# Ocreeb_MK_2__faders_half__schematic.net
KiCad netlist of a schematic drawn in EAGLE
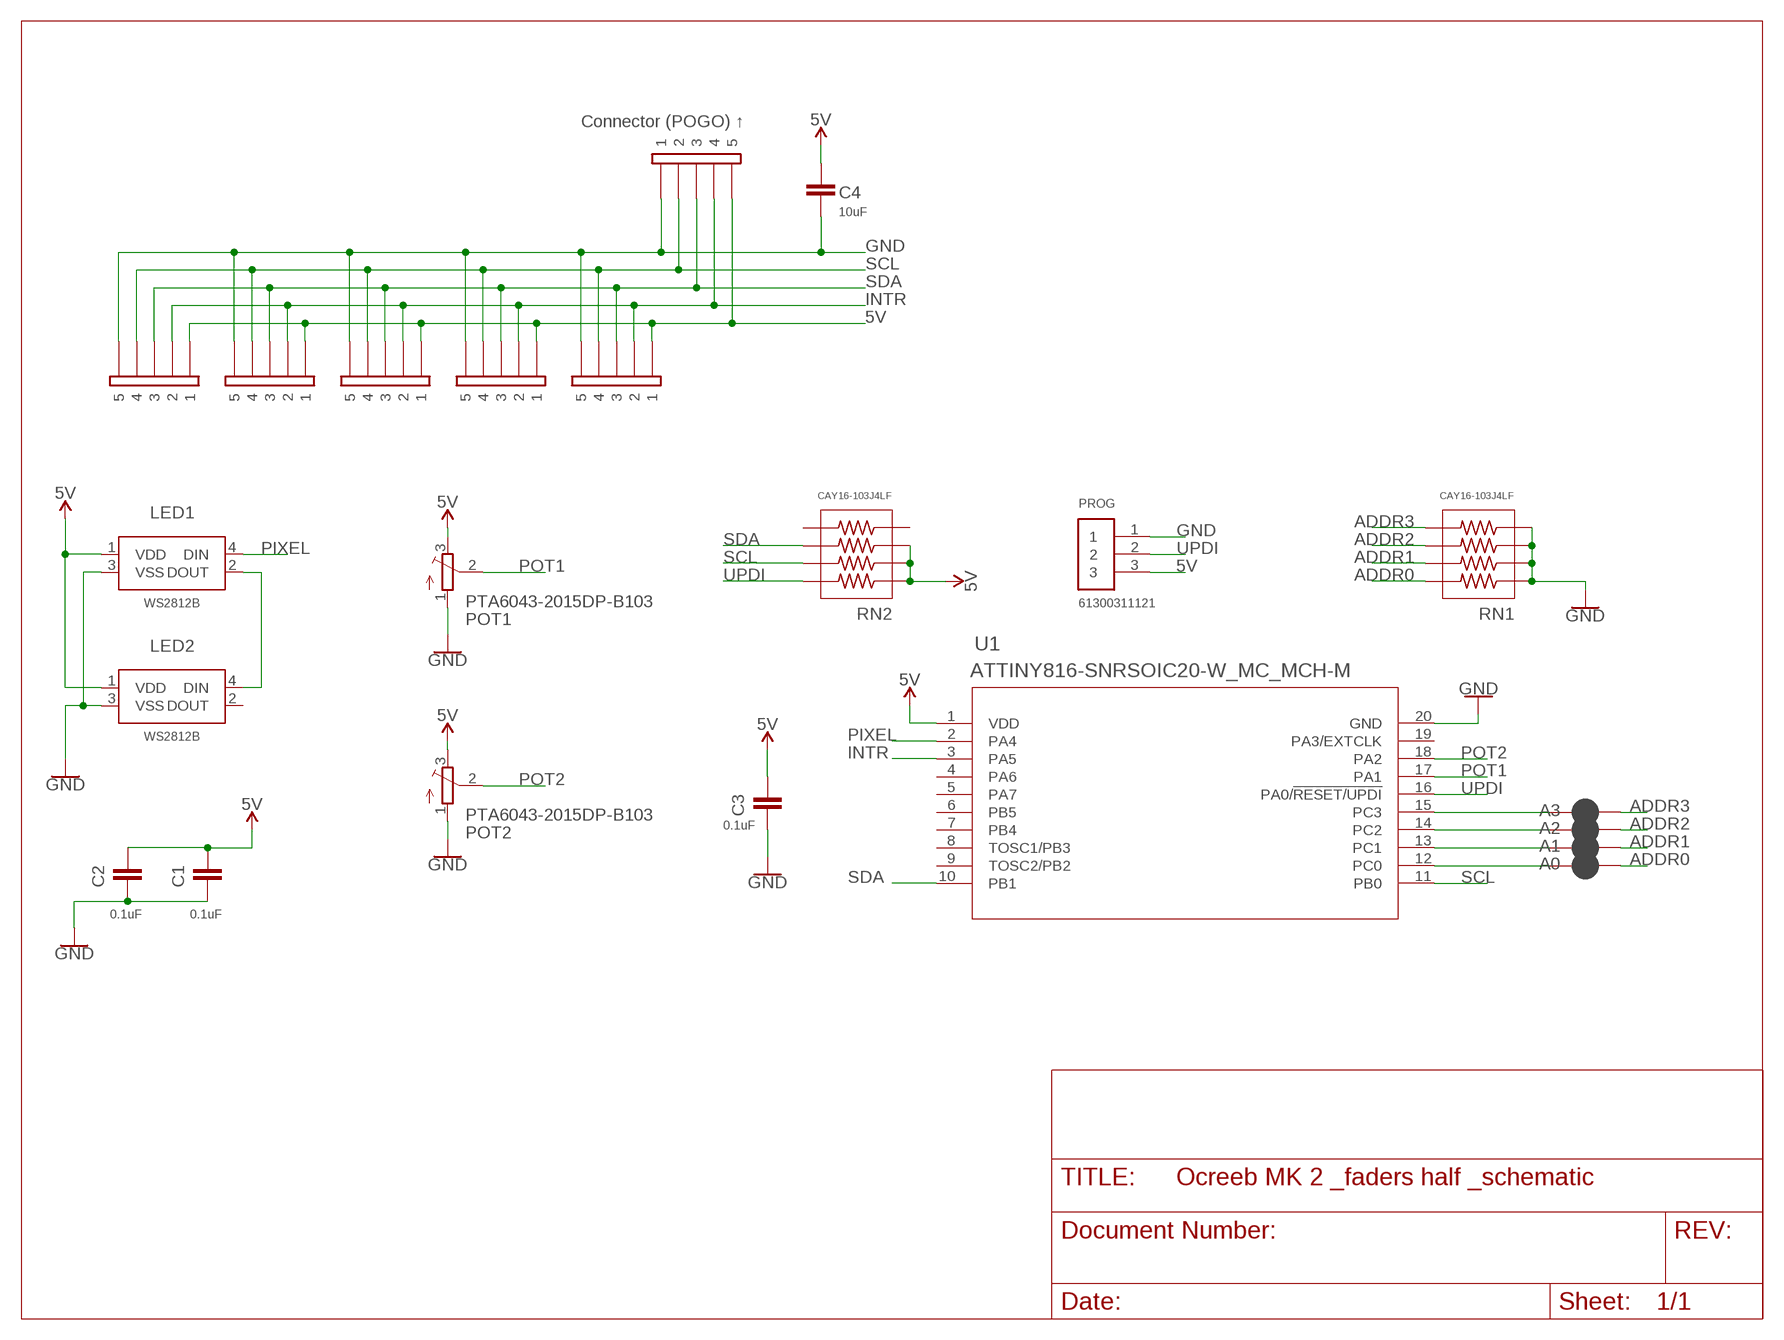
[diagram p0: schematic, sheet 1]

(export (version "E")
  (design (tool "Eeschema 10.0.6"))
  (components
    (comp (ref "A0")
      (value "JUMPER-SMT_2_NC_PASTE_SILK")
      (footprint "eagle-import:SMT-JUMPER_2_NC_PASTE_SILK")
      (libsource (lib "eagle-import") (part "JUMPER-SMT_2_NC_PASTE_SILK"))
    )
    (comp (ref "A1")
      (value "JUMPER-SMT_2_NC_PASTE_SILK")
      (footprint "eagle-import:SMT-JUMPER_2_NC_PASTE_SILK")
      (libsource (lib "eagle-import") (part "JUMPER-SMT_2_NC_PASTE_SILK"))
    )
    (comp (ref "A2")
      (value "JUMPER-SMT_2_NC_PASTE_SILK")
      (footprint "eagle-import:SMT-JUMPER_2_NC_PASTE_SILK")
      (libsource (lib "eagle-import") (part "JUMPER-SMT_2_NC_PASTE_SILK"))
    )
    (comp (ref "A3")
      (value "JUMPER-SMT_2_NC_PASTE_SILK")
      (footprint "eagle-import:SMT-JUMPER_2_NC_PASTE_SILK")
      (libsource (lib "eagle-import") (part "JUMPER-SMT_2_NC_PASTE_SILK"))
    )
    (comp (ref "C1")
      (value "0.1uF")
      (footprint "eagle-import:CAPC1608X85")
      (libsource (lib "eagle-import") (part "CCHIP-0603(1608-METRIC)_"))
    )
    (comp (ref "C2")
      (value "0.1uF")
      (footprint "eagle-import:CAPC1608X85")
      (libsource (lib "eagle-import") (part "CCHIP-0603(1608-METRIC)_"))
    )
    (comp (ref "C3")
      (value "0.1uF")
      (footprint "eagle-import:CAPC1608X85")
      (libsource (lib "eagle-import") (part "CCHIP-0603(1608-METRIC)_"))
    )
    (comp (ref "C4")
      (value "10uF")
      (footprint "eagle-import:CAPC2012X110")
      (libsource (lib "eagle-import") (part "CCHIP-0805(2012-METRIC)_"))
    )
    (comp (ref "LED1")
      (value "WS2812B")
      (footprint "eagle-import:WS2812B")
      (fields (field (name "MANUFACTURER") "Worldsemi"))
      (libsource (lib "eagle-import") (part "WS2812B"))
    )
    (comp (ref "LED2")
      (value "WS2812B")
      (footprint "eagle-import:WS2812B")
      (fields (field (name "MANUFACTURER") "Worldsemi"))
      (libsource (lib "eagle-import") (part "WS2812B"))
    )
    (comp (ref "POT1")
      (value "PTA6043-2015DP-B103")
      (footprint "eagle-import:PTA6043-2015DP-B103")
      (fields (field (name "MF") "Bourns") (field (name "MP") "PTA6043-2015DPB103"))
      (libsource (lib "eagle-import") (part "PTA6043-2015DP-B103"))
    )
    (comp (ref "POT2")
      (value "PTA6043-2015DP-B103")
      (footprint "eagle-import:PTA6043-2015DP-B103")
      (fields (field (name "MF") "Bourns") (field (name "MP") "PTA6043-2015DPB103"))
      (libsource (lib "eagle-import") (part "PTA6043-2015DP-B103"))
    )
    (comp (ref "PROG")
      (value "61300311121")
      (footprint "eagle-import:61300311121")
      (fields
        (field (name "DIGI_KEY_PART_NUMBER") "732-5316-ND")
        (field (name "MANUFACTURER") "Wurth Electronics Inc.")
        (field (name "CREATED_BY") "PCBLayout.com")
      )
      (libsource (lib "eagle-import") (part "61300311121"))
    )
    (comp (ref "RN1")
      (value "CAY16-103J4LF")
      (footprint "eagle-import:RESCAF80P320X160X60-8N")
      (fields (field (name "DIGIKEY_PART_NUMBER") "CAY16-103J4LFTR-ND") (field (name "MF") "Bourns"))
      (libsource (lib "eagle-import") (part "CAY16-103J4LF"))
    )
    (comp (ref "RN2")
      (value "CAY16-103J4LF")
      (footprint "eagle-import:RESCAF80P320X160X60-8N")
      (fields (field (name "DIGIKEY_PART_NUMBER") "CAY16-103J4LFTR-ND") (field (name "MF") "Bourns"))
      (libsource (lib "eagle-import") (part "CAY16-103J4LF"))
    )
    (comp (ref "U$1")
      (value "5PIN_EDGE5_POGO_EDGE_OUT_")
      (footprint "eagle-import:5_POGO_EDGE")
      (libsource (lib "eagle-import") (part "5PIN_EDGE5_POGO_EDGE_OUT_"))
    )
    (comp (ref "U$2")
      (value "5PIN_EDGE")
      (footprint "eagle-import:5_POGO_EDGE")
      (libsource (lib "eagle-import") (part "5PIN_EDGE"))
    )
    (comp (ref "U$3")
      (value "5PIN_EDGE")
      (footprint "eagle-import:5_POGO_EDGE")
      (libsource (lib "eagle-import") (part "5PIN_EDGE"))
    )
    (comp (ref "U$4")
      (value "5PIN_EDGE")
      (footprint "eagle-import:5_POGO_EDGE")
      (libsource (lib "eagle-import") (part "5PIN_EDGE"))
    )
    (comp (ref "U$5")
      (value "5PIN_EDGE")
      (footprint "eagle-import:5_POGO_EDGE")
      (libsource (lib "eagle-import") (part "5PIN_EDGE"))
    )
    (comp (ref "U$6")
      (value "5PIN_EDGE")
      (footprint "eagle-import:5_POGO_EDGE")
      (libsource (lib "eagle-import") (part "5PIN_EDGE"))
    )
    (comp (ref "U1")
      (value "ATTINY816-SNRSOIC20-W_MC_MCH-M")
      (footprint "eagle-import:SOIC20-W_MC_MCH-M")
      (fields
        (field (name "MANUFACTURER_PART_NUMBER") "ATTINY816-SNR")
        (field (name "COPYRIGHT") "Copyright (C) 2023 Ultra Librarian. All rights reserved.")
      )
      (libsource (lib "eagle-import") (part "ATTINY816-SNRSOIC20-W_MC_MCH-M"))
    )
  )
  (nets
    (net (code "1") (name "/ADDR0") (class "Default")
      (node (ref "A0") (pin "1") (pinfunction "1_1") (pintype "passive"))
      (node (ref "RN1") (pin "8") (pinfunction "8_8") (pintype "passive"))
    )
    (net (code "2") (name "/ADDR1") (class "Default")
      (node (ref "A1") (pin "1") (pinfunction "1_1") (pintype "passive"))
      (node (ref "RN1") (pin "7") (pinfunction "7_7") (pintype "passive"))
    )
    (net (code "3") (name "/ADDR2") (class "Default")
      (node (ref "A2") (pin "1") (pinfunction "1_1") (pintype "passive"))
      (node (ref "RN1") (pin "6") (pinfunction "6_6") (pintype "passive"))
    )
    (net (code "4") (name "/ADDR3") (class "Default")
      (node (ref "A3") (pin "1") (pinfunction "1_1") (pintype "passive"))
      (node (ref "RN1") (pin "5") (pinfunction "5_5") (pintype "passive"))
    )
    (net (code "5") (name "/INTR") (class "Default")
      (node (ref "U$1") (pin "4") (pinfunction "4_4") (pintype "bidirectional"))
      (node (ref "U$2") (pin "2") (pinfunction "2_2") (pintype "bidirectional"))
      (node (ref "U$3") (pin "2") (pinfunction "2_2") (pintype "bidirectional"))
      (node (ref "U$4") (pin "2") (pinfunction "2_2") (pintype "bidirectional"))
      (node (ref "U$5") (pin "2") (pinfunction "2_2") (pintype "bidirectional"))
      (node (ref "U$6") (pin "2") (pinfunction "2_2") (pintype "bidirectional"))
      (node (ref "U1") (pin "3") (pinfunction "PA5_3") (pintype "bidirectional"))
    )
    (net (code "6") (name "/PIXEL") (class "Default")
      (node (ref "LED1") (pin "4") (pinfunction "DIN_4") (pintype "input"))
      (node (ref "U1") (pin "2") (pinfunction "PA4_2") (pintype "bidirectional"))
    )
    (net (code "7") (name "/POT1") (class "Default")
      (node (ref "POT1") (pin "2") (pinfunction "2_2") (pintype "passive"))
      (node (ref "U1") (pin "17") (pinfunction "PA1_17") (pintype "bidirectional"))
    )
    (net (code "8") (name "/POT2") (class "Default")
      (node (ref "POT2") (pin "2") (pinfunction "2_2") (pintype "passive"))
      (node (ref "U1") (pin "18") (pinfunction "PA2_18") (pintype "bidirectional"))
    )
    (net (code "9") (name "/SCL") (class "Default")
      (node (ref "RN2") (pin "7") (pinfunction "7_7") (pintype "passive"))
      (node (ref "U$1") (pin "2") (pinfunction "2_2") (pintype "bidirectional"))
      (node (ref "U$2") (pin "4") (pinfunction "4_4") (pintype "bidirectional"))
      (node (ref "U$3") (pin "4") (pinfunction "4_4") (pintype "bidirectional"))
      (node (ref "U$4") (pin "4") (pinfunction "4_4") (pintype "bidirectional"))
      (node (ref "U$5") (pin "4") (pinfunction "4_4") (pintype "bidirectional"))
      (node (ref "U$6") (pin "4") (pinfunction "4_4") (pintype "bidirectional"))
      (node (ref "U1") (pin "11") (pinfunction "PB0_11") (pintype "bidirectional"))
    )
    (net (code "10") (name "/SDA") (class "Default")
      (node (ref "RN2") (pin "6") (pinfunction "6_6") (pintype "passive"))
      (node (ref "U$1") (pin "3") (pinfunction "3_3") (pintype "bidirectional"))
      (node (ref "U$2") (pin "3") (pinfunction "3_3") (pintype "bidirectional"))
      (node (ref "U$3") (pin "3") (pinfunction "3_3") (pintype "bidirectional"))
      (node (ref "U$4") (pin "3") (pinfunction "3_3") (pintype "bidirectional"))
      (node (ref "U$5") (pin "3") (pinfunction "3_3") (pintype "bidirectional"))
      (node (ref "U$6") (pin "3") (pinfunction "3_3") (pintype "bidirectional"))
      (node (ref "U1") (pin "10") (pinfunction "PB1_10") (pintype "bidirectional"))
    )
    (net (code "11") (name "/UPDI") (class "Default")
      (node (ref "PROG") (pin "2") (pinfunction "2_2") (pintype "passive"))
      (node (ref "RN2") (pin "8") (pinfunction "8_8") (pintype "passive"))
      (node (ref "U1") (pin "16") (pinfunction "PA0/~{RESET/UPDI}_16") (pintype "bidirectional"))
    )
    (net (code "12") (name "5V") (class "Default")
      (node (ref "C1") (pin "2") (pinfunction "2_2") (pintype "passive"))
      (node (ref "C2") (pin "2") (pinfunction "2_2") (pintype "passive"))
      (node (ref "C3") (pin "2") (pinfunction "2_2") (pintype "passive"))
      (node (ref "C4") (pin "2") (pinfunction "2_2") (pintype "passive"))
      (node (ref "LED1") (pin "1") (pinfunction "VDD_1") (pintype "power_in"))
      (node (ref "LED2") (pin "1") (pinfunction "VDD_1") (pintype "power_in"))
      (node (ref "POT1") (pin "3") (pinfunction "3_3") (pintype "passive"))
      (node (ref "POT2") (pin "3") (pinfunction "3_3") (pintype "passive"))
      (node (ref "PROG") (pin "3") (pinfunction "3_3") (pintype "passive"))
      (node (ref "RN2") (pin "1") (pinfunction "1_1") (pintype "passive"))
      (node (ref "RN2") (pin "2") (pinfunction "2_2") (pintype "passive"))
      (node (ref "RN2") (pin "3") (pinfunction "3_3") (pintype "passive"))
      (node (ref "U$1") (pin "5") (pinfunction "5_5") (pintype "bidirectional"))
      (node (ref "U$2") (pin "1") (pinfunction "1_1") (pintype "bidirectional"))
      (node (ref "U$3") (pin "1") (pinfunction "1_1") (pintype "bidirectional"))
      (node (ref "U$4") (pin "1") (pinfunction "1_1") (pintype "bidirectional"))
      (node (ref "U$5") (pin "1") (pinfunction "1_1") (pintype "bidirectional"))
      (node (ref "U$6") (pin "1") (pinfunction "1_1") (pintype "bidirectional"))
      (node (ref "U1") (pin "1") (pinfunction "VDD_1") (pintype "power_in"))
    )
    (net (code "13") (name "GND") (class "Default")
      (node (ref "C1") (pin "1") (pinfunction "1_1") (pintype "passive"))
      (node (ref "C2") (pin "1") (pinfunction "1_1") (pintype "passive"))
      (node (ref "C3") (pin "1") (pinfunction "1_1") (pintype "passive"))
      (node (ref "C4") (pin "1") (pinfunction "1_1") (pintype "passive"))
      (node (ref "LED1") (pin "3") (pinfunction "VSS_3") (pintype "power_in"))
      (node (ref "LED2") (pin "3") (pinfunction "VSS_3") (pintype "power_in"))
      (node (ref "POT1") (pin "1") (pinfunction "1_1") (pintype "passive"))
      (node (ref "POT2") (pin "1") (pinfunction "1_1") (pintype "passive"))
      (node (ref "PROG") (pin "1") (pinfunction "1_1") (pintype "passive"))
      (node (ref "RN1") (pin "1") (pinfunction "1_1") (pintype "passive"))
      (node (ref "RN1") (pin "2") (pinfunction "2_2") (pintype "passive"))
      (node (ref "RN1") (pin "3") (pinfunction "3_3") (pintype "passive"))
      (node (ref "RN1") (pin "4") (pinfunction "4_4") (pintype "passive"))
      (node (ref "U$1") (pin "1") (pinfunction "1_1") (pintype "bidirectional"))
      (node (ref "U$2") (pin "5") (pinfunction "5_5") (pintype "bidirectional"))
      (node (ref "U$3") (pin "5") (pinfunction "5_5") (pintype "bidirectional"))
      (node (ref "U$4") (pin "5") (pinfunction "5_5") (pintype "bidirectional"))
      (node (ref "U$5") (pin "5") (pinfunction "5_5") (pintype "bidirectional"))
      (node (ref "U$6") (pin "5") (pinfunction "5_5") (pintype "bidirectional"))
      (node (ref "U1") (pin "20") (pinfunction "GND_20") (pintype "passive"))
    )
    (net (code "14") (name "Net-(LED1-DOUT)") (class "Default")
      (node (ref "LED1") (pin "2") (pinfunction "DOUT_2") (pintype "output"))
      (node (ref "LED2") (pin "4") (pinfunction "DIN_4") (pintype "input"))
    )
    (net (code "15") (name "Net-(U1-PC0)") (class "Default")
      (node (ref "A0") (pin "2") (pinfunction "2_2") (pintype "passive"))
      (node (ref "U1") (pin "12") (pinfunction "PC0_12") (pintype "bidirectional"))
    )
    (net (code "16") (name "Net-(U1-PC1)") (class "Default")
      (node (ref "A1") (pin "2") (pinfunction "2_2") (pintype "passive"))
      (node (ref "U1") (pin "13") (pinfunction "PC1_13") (pintype "bidirectional"))
    )
    (net (code "17") (name "Net-(U1-PC2)") (class "Default")
      (node (ref "A2") (pin "2") (pinfunction "2_2") (pintype "passive"))
      (node (ref "U1") (pin "14") (pinfunction "PC2_14") (pintype "bidirectional"))
    )
    (net (code "18") (name "Net-(U1-PC3)") (class "Default")
      (node (ref "A3") (pin "2") (pinfunction "2_2") (pintype "passive"))
      (node (ref "U1") (pin "15") (pinfunction "PC3_15") (pintype "bidirectional"))
    )
    (net (code "19") (name "unconnected-(LED2-DOUT-Pad2)") (class "Default")
      (node (ref "LED2") (pin "2") (pinfunction "DOUT_2") (pintype "output"))
    )
    (net (code "20") (name "unconnected-(RN2-Pad4)") (class "Default")
      (node (ref "RN2") (pin "4") (pinfunction "4_4") (pintype "passive"))
    )
    (net (code "21") (name "unconnected-(RN2-Pad5)") (class "Default")
      (node (ref "RN2") (pin "5") (pinfunction "5_5") (pintype "passive"))
    )
    (net (code "22") (name "unconnected-(U1-PA3{slash}EXTCLK-Pad19)") (class "Default")
      (node (ref "U1") (pin "19") (pinfunction "PA3/EXTCLK_19") (pintype "bidirectional"))
    )
    (net (code "23") (name "unconnected-(U1-PA6-Pad4)") (class "Default")
      (node (ref "U1") (pin "4") (pinfunction "PA6_4") (pintype "bidirectional"))
    )
    (net (code "24") (name "unconnected-(U1-PA7-Pad5)") (class "Default")
      (node (ref "U1") (pin "5") (pinfunction "PA7_5") (pintype "bidirectional"))
    )
    (net (code "25") (name "unconnected-(U1-PB4-Pad7)") (class "Default")
      (node (ref "U1") (pin "7") (pinfunction "PB4_7") (pintype "bidirectional"))
    )
    (net (code "26") (name "unconnected-(U1-PB5-Pad6)") (class "Default")
      (node (ref "U1") (pin "6") (pinfunction "PB5_6") (pintype "bidirectional"))
    )
    (net (code "27") (name "unconnected-(U1-TOSC1{slash}PB3-Pad8)") (class "Default")
      (node (ref "U1") (pin "8") (pinfunction "TOSC1/PB3_8") (pintype "bidirectional"))
    )
    (net (code "28") (name "unconnected-(U1-TOSC2{slash}PB2-Pad9)") (class "Default")
      (node (ref "U1") (pin "9") (pinfunction "TOSC2/PB2_9") (pintype "bidirectional"))
    )
  )
)
